# expansion_module_dual_potentiometer.net
KiCad netlist of a schematic drawn in EAGLE
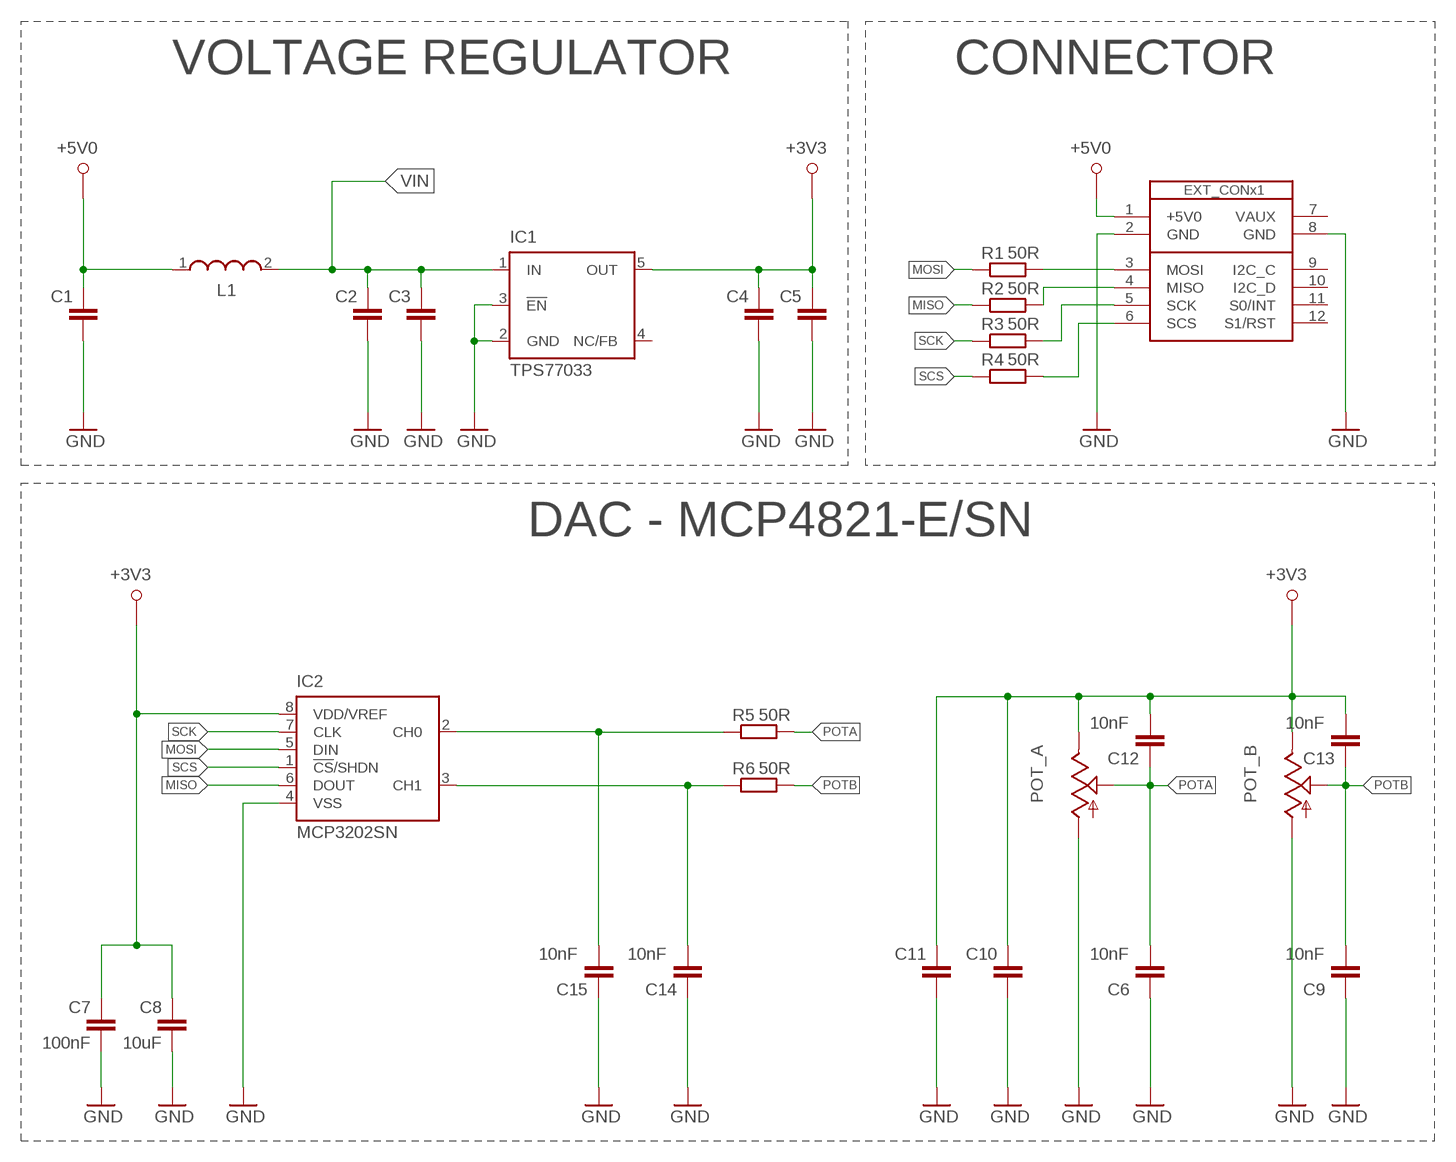
[diagram p0: schematic, sheet 1]

(export (version "E")
  (design (tool "Eeschema 10.0.6"))
  (components
    (comp (ref "C1")
      (value "C-EUC0805")
      (footprint "eagle-import:C0805")
      (libsource (lib "eagle-import") (part "C-EUC0805"))
    )
    (comp (ref "C2")
      (value "C-EUC0805")
      (footprint "eagle-import:C0805")
      (libsource (lib "eagle-import") (part "C-EUC0805"))
    )
    (comp (ref "C3")
      (value "C-EUC0805")
      (footprint "eagle-import:C0805")
      (libsource (lib "eagle-import") (part "C-EUC0805"))
    )
    (comp (ref "C4")
      (value "C-EUC0805")
      (footprint "eagle-import:C0805")
      (libsource (lib "eagle-import") (part "C-EUC0805"))
    )
    (comp (ref "C5")
      (value "C-EUC0805")
      (footprint "eagle-import:C0805")
      (libsource (lib "eagle-import") (part "C-EUC0805"))
    )
    (comp (ref "C6")
      (value "10nF")
      (footprint "eagle-import:C0805")
      (libsource (lib "eagle-import") (part "C-EUC0805"))
    )
    (comp (ref "C7")
      (value "100nF")
      (footprint "eagle-import:C0805")
      (libsource (lib "eagle-import") (part "C-EUC0805"))
    )
    (comp (ref "C8")
      (value "10uF")
      (footprint "eagle-import:C0805")
      (libsource (lib "eagle-import") (part "C-EUC0805"))
    )
    (comp (ref "C9")
      (value "10nF")
      (footprint "eagle-import:C0805")
      (libsource (lib "eagle-import") (part "C-EUC0805"))
    )
    (comp (ref "C10")
      (value "C-EUC0805")
      (footprint "eagle-import:C0805")
      (libsource (lib "eagle-import") (part "C-EUC0805"))
    )
    (comp (ref "C11")
      (value "C-EUC0805")
      (footprint "eagle-import:C0805")
      (libsource (lib "eagle-import") (part "C-EUC0805"))
    )
    (comp (ref "C12")
      (value "10nF")
      (footprint "eagle-import:C0805")
      (libsource (lib "eagle-import") (part "C-EUC0805"))
    )
    (comp (ref "C13")
      (value "10nF")
      (footprint "eagle-import:C0805")
      (libsource (lib "eagle-import") (part "C-EUC0805"))
    )
    (comp (ref "C14")
      (value "10nF")
      (footprint "eagle-import:C0805")
      (libsource (lib "eagle-import") (part "C-EUC0805"))
    )
    (comp (ref "C15")
      (value "10nF")
      (footprint "eagle-import:C0805")
      (libsource (lib "eagle-import") (part "C-EUC0805"))
    )
    (comp (ref "IC1")
      (value "TPS77033")
      (footprint "eagle-import:SOT23-DBV")
      (fields (field (name "MF") "TEXAS INSTRUMENTS") (field (name "MPN") "TPS77033DBVT"))
      (libsource (lib "eagle-import") (part "TPS77033"))
    )
    (comp (ref "IC2")
      (value "MCP3202SN")
      (footprint "eagle-import:SO-08")
      (fields (field (name "MF") "MICROCHIP") (field (name "MPN") "MCP3202-CI/SN"))
      (libsource (lib "eagle-import") (part "MCP3202SN"))
    )
    (comp (ref "L1")
      (value "WE-LQ_1210")
      (footprint "eagle-import:WE-LQ_M")
      (libsource (lib "eagle-import") (part "WE-LQ_1210"))
    )
    (comp (ref "POT_A")
      (value "9MM_SNAP-IN_POT_")
      (footprint "eagle-import:9MM_SNAP-IN_POT")
      (libsource (lib "eagle-import") (part "9MM_SNAP-IN_POT_"))
    )
    (comp (ref "POT_B")
      (value "9MM_SNAP-IN_POT_")
      (footprint "eagle-import:9MM_SNAP-IN_POT")
      (libsource (lib "eagle-import") (part "9MM_SNAP-IN_POT_"))
    )
    (comp (ref "R1")
      (value "50R")
      (footprint "eagle-import:R0805")
      (libsource (lib "eagle-import") (part "R-EU_R0805"))
    )
    (comp (ref "R2")
      (value "50R")
      (footprint "eagle-import:R0805")
      (libsource (lib "eagle-import") (part "R-EU_R0805"))
    )
    (comp (ref "R3")
      (value "50R")
      (footprint "eagle-import:R0805")
      (libsource (lib "eagle-import") (part "R-EU_R0805"))
    )
    (comp (ref "R4")
      (value "50R")
      (footprint "eagle-import:R0805")
      (libsource (lib "eagle-import") (part "R-EU_R0805"))
    )
    (comp (ref "R5")
      (value "50R")
      (footprint "eagle-import:R0805")
      (libsource (lib "eagle-import") (part "R-EU_R0805"))
    )
    (comp (ref "R6")
      (value "50R")
      (footprint "eagle-import:R0805")
      (libsource (lib "eagle-import") (part "R-EU_R0805"))
    )
    (comp (ref "U$1")
      (value "SB_EXT_CON_X1_SPI")
      (footprint "eagle-import:SB_EXT_CON_X1_FULL")
      (libsource (lib "eagle-import") (part "SB_EXT_CON_X1_SPI"))
    )
  )
  (nets
    (net (code "1") (name "+3V3") (class "Default")
      (node (ref "C10") (pin "2") (pinfunction "2_2") (pintype "passive"))
      (node (ref "C11") (pin "2") (pinfunction "2_2") (pintype "passive"))
      (node (ref "C12") (pin "1") (pinfunction "1_1") (pintype "passive"))
      (node (ref "C13") (pin "1") (pinfunction "1_1") (pintype "passive"))
      (node (ref "C4") (pin "2") (pinfunction "2_2") (pintype "passive"))
      (node (ref "C5") (pin "2") (pinfunction "2_2") (pintype "passive"))
      (node (ref "C7") (pin "2") (pinfunction "2_2") (pintype "passive"))
      (node (ref "C8") (pin "2") (pinfunction "2_2") (pintype "passive"))
      (node (ref "IC1") (pin "5") (pinfunction "OUT_5") (pintype "passive"))
      (node (ref "IC2") (pin "8") (pinfunction "VDD/VREF_8") (pintype "input"))
      (node (ref "POT_A") (pin "3") (pinfunction "E_3") (pintype "passive"))
      (node (ref "POT_B") (pin "3") (pinfunction "E_3") (pintype "passive"))
    )
    (net (code "2") (name "+5V0") (class "Default")
      (node (ref "C1") (pin "2") (pinfunction "2_2") (pintype "passive"))
      (node (ref "L1") (pin "1") (pinfunction "1_1") (pintype "passive"))
      (node (ref "U$1") (pin "1") (pinfunction "+5V0_1") (pintype "bidirectional"))
    )
    (net (code "3") (name "GND") (class "Default")
      (node (ref "C1") (pin "1") (pinfunction "1_1") (pintype "passive"))
      (node (ref "C10") (pin "1") (pinfunction "1_1") (pintype "passive"))
      (node (ref "C11") (pin "1") (pinfunction "1_1") (pintype "passive"))
      (node (ref "C14") (pin "2") (pinfunction "2_2") (pintype "passive"))
      (node (ref "C15") (pin "2") (pinfunction "2_2") (pintype "passive"))
      (node (ref "C2") (pin "1") (pinfunction "1_1") (pintype "passive"))
      (node (ref "C3") (pin "1") (pinfunction "1_1") (pintype "passive"))
      (node (ref "C4") (pin "1") (pinfunction "1_1") (pintype "passive"))
      (node (ref "C5") (pin "1") (pinfunction "1_1") (pintype "passive"))
      (node (ref "C6") (pin "2") (pinfunction "2_2") (pintype "passive"))
      (node (ref "C7") (pin "1") (pinfunction "1_1") (pintype "passive"))
      (node (ref "C8") (pin "1") (pinfunction "1_1") (pintype "passive"))
      (node (ref "C9") (pin "2") (pinfunction "2_2") (pintype "passive"))
      (node (ref "IC1") (pin "2") (pinfunction "GND_2") (pintype "power_in"))
      (node (ref "IC1") (pin "3") (pinfunction "~{EN}_3") (pintype "input"))
      (node (ref "IC2") (pin "4") (pinfunction "VSS_4") (pintype "input"))
      (node (ref "POT_A") (pin "1") (pinfunction "A_1") (pintype "passive"))
      (node (ref "POT_B") (pin "1") (pinfunction "A_1") (pintype "passive"))
      (node (ref "U$1") (pin "2") (pinfunction "GND_2") (pintype "bidirectional"))
      (node (ref "U$1") (pin "8") (pinfunction "GND_8") (pintype "bidirectional"))
    )
    (net (code "4") (name "MISO") (class "Default")
      (node (ref "IC2") (pin "6") (pinfunction "DOUT_6") (pintype "input"))
      (node (ref "R2") (pin "1") (pinfunction "1_1") (pintype "passive"))
    )
    (net (code "5") (name "MOSI") (class "Default")
      (node (ref "IC2") (pin "5") (pinfunction "DIN_5") (pintype "input"))
      (node (ref "R1") (pin "1") (pinfunction "1_1") (pintype "passive"))
    )
    (net (code "6") (name "Net-(IC2-CH0)") (class "Default")
      (node (ref "C15") (pin "1") (pinfunction "1_1") (pintype "passive"))
      (node (ref "IC2") (pin "2") (pinfunction "CH0_2") (pintype "input"))
      (node (ref "R5") (pin "1") (pinfunction "1_1") (pintype "passive"))
    )
    (net (code "7") (name "Net-(IC2-CH1)") (class "Default")
      (node (ref "C14") (pin "1") (pinfunction "1_1") (pintype "passive"))
      (node (ref "IC2") (pin "3") (pinfunction "CH1_3") (pintype "input"))
      (node (ref "R6") (pin "1") (pinfunction "1_1") (pintype "passive"))
    )
    (net (code "8") (name "Net-(U$1-MISO)") (class "Default")
      (node (ref "R2") (pin "2") (pinfunction "2_2") (pintype "passive"))
      (node (ref "U$1") (pin "4") (pinfunction "MISO_4") (pintype "bidirectional"))
    )
    (net (code "9") (name "Net-(U$1-MOSI)") (class "Default")
      (node (ref "R1") (pin "2") (pinfunction "2_2") (pintype "passive"))
      (node (ref "U$1") (pin "3") (pinfunction "MOSI_3") (pintype "bidirectional"))
    )
    (net (code "10") (name "Net-(U$1-SCK)") (class "Default")
      (node (ref "R3") (pin "2") (pinfunction "2_2") (pintype "passive"))
      (node (ref "U$1") (pin "5") (pinfunction "SCK_5") (pintype "bidirectional"))
    )
    (net (code "11") (name "Net-(U$1-SCS)") (class "Default")
      (node (ref "R4") (pin "2") (pinfunction "2_2") (pintype "passive"))
      (node (ref "U$1") (pin "6") (pinfunction "SCS_6") (pintype "bidirectional"))
    )
    (net (code "12") (name "POTA") (class "Default")
      (node (ref "C12") (pin "2") (pinfunction "2_2") (pintype "passive"))
      (node (ref "C6") (pin "1") (pinfunction "1_1") (pintype "passive"))
      (node (ref "POT_A") (pin "2") (pinfunction "S_2") (pintype "passive"))
      (node (ref "R5") (pin "2") (pinfunction "2_2") (pintype "passive"))
    )
    (net (code "13") (name "POTB") (class "Default")
      (node (ref "C13") (pin "2") (pinfunction "2_2") (pintype "passive"))
      (node (ref "C9") (pin "1") (pinfunction "1_1") (pintype "passive"))
      (node (ref "POT_B") (pin "2") (pinfunction "S_2") (pintype "passive"))
      (node (ref "R6") (pin "2") (pinfunction "2_2") (pintype "passive"))
    )
    (net (code "14") (name "SCK") (class "Default")
      (node (ref "IC2") (pin "7") (pinfunction "CLK_7") (pintype "input"))
      (node (ref "R3") (pin "1") (pinfunction "1_1") (pintype "passive"))
    )
    (net (code "15") (name "SCS") (class "Default")
      (node (ref "IC2") (pin "1") (pinfunction "~{CS}/SHDN_1") (pintype "input"))
      (node (ref "R4") (pin "1") (pinfunction "1_1") (pintype "passive"))
    )
    (net (code "16") (name "VIN") (class "Default")
      (node (ref "C2") (pin "2") (pinfunction "2_2") (pintype "passive"))
      (node (ref "C3") (pin "2") (pinfunction "2_2") (pintype "passive"))
      (node (ref "IC1") (pin "1") (pinfunction "IN_1") (pintype "input"))
      (node (ref "L1") (pin "2") (pinfunction "2_2") (pintype "passive"))
    )
    (net (code "17") (name "unconnected-(IC1-NC{slash}FB-Pad4)") (class "Default")
      (node (ref "IC1") (pin "4") (pinfunction "NC/FB_4") (pintype "passive"))
    )
    (net (code "18") (name "unconnected-(U$1-I2C_C-Pad9)") (class "Default")
      (node (ref "U$1") (pin "9") (pinfunction "I2C_C_9") (pintype "bidirectional"))
    )
    (net (code "19") (name "unconnected-(U$1-I2C_D-Pad10)") (class "Default")
      (node (ref "U$1") (pin "10") (pinfunction "I2C_D_10") (pintype "bidirectional"))
    )
    (net (code "20") (name "unconnected-(U$1-S0{slash}INT-Pad11)") (class "Default")
      (node (ref "U$1") (pin "11") (pinfunction "S0/INT_11") (pintype "bidirectional"))
    )
    (net (code "21") (name "unconnected-(U$1-S1{slash}RST-Pad12)") (class "Default")
      (node (ref "U$1") (pin "12") (pinfunction "S1/RST_12") (pintype "bidirectional"))
    )
    (net (code "22") (name "unconnected-(U$1-VAUX-Pad7)") (class "Default")
      (node (ref "U$1") (pin "7") (pinfunction "VAUX_7") (pintype "bidirectional"))
    )
  )
)
